# HGD_MCU_v0_2_-20200901.net
KiCad netlist of a schematic drawn in Altium Designer
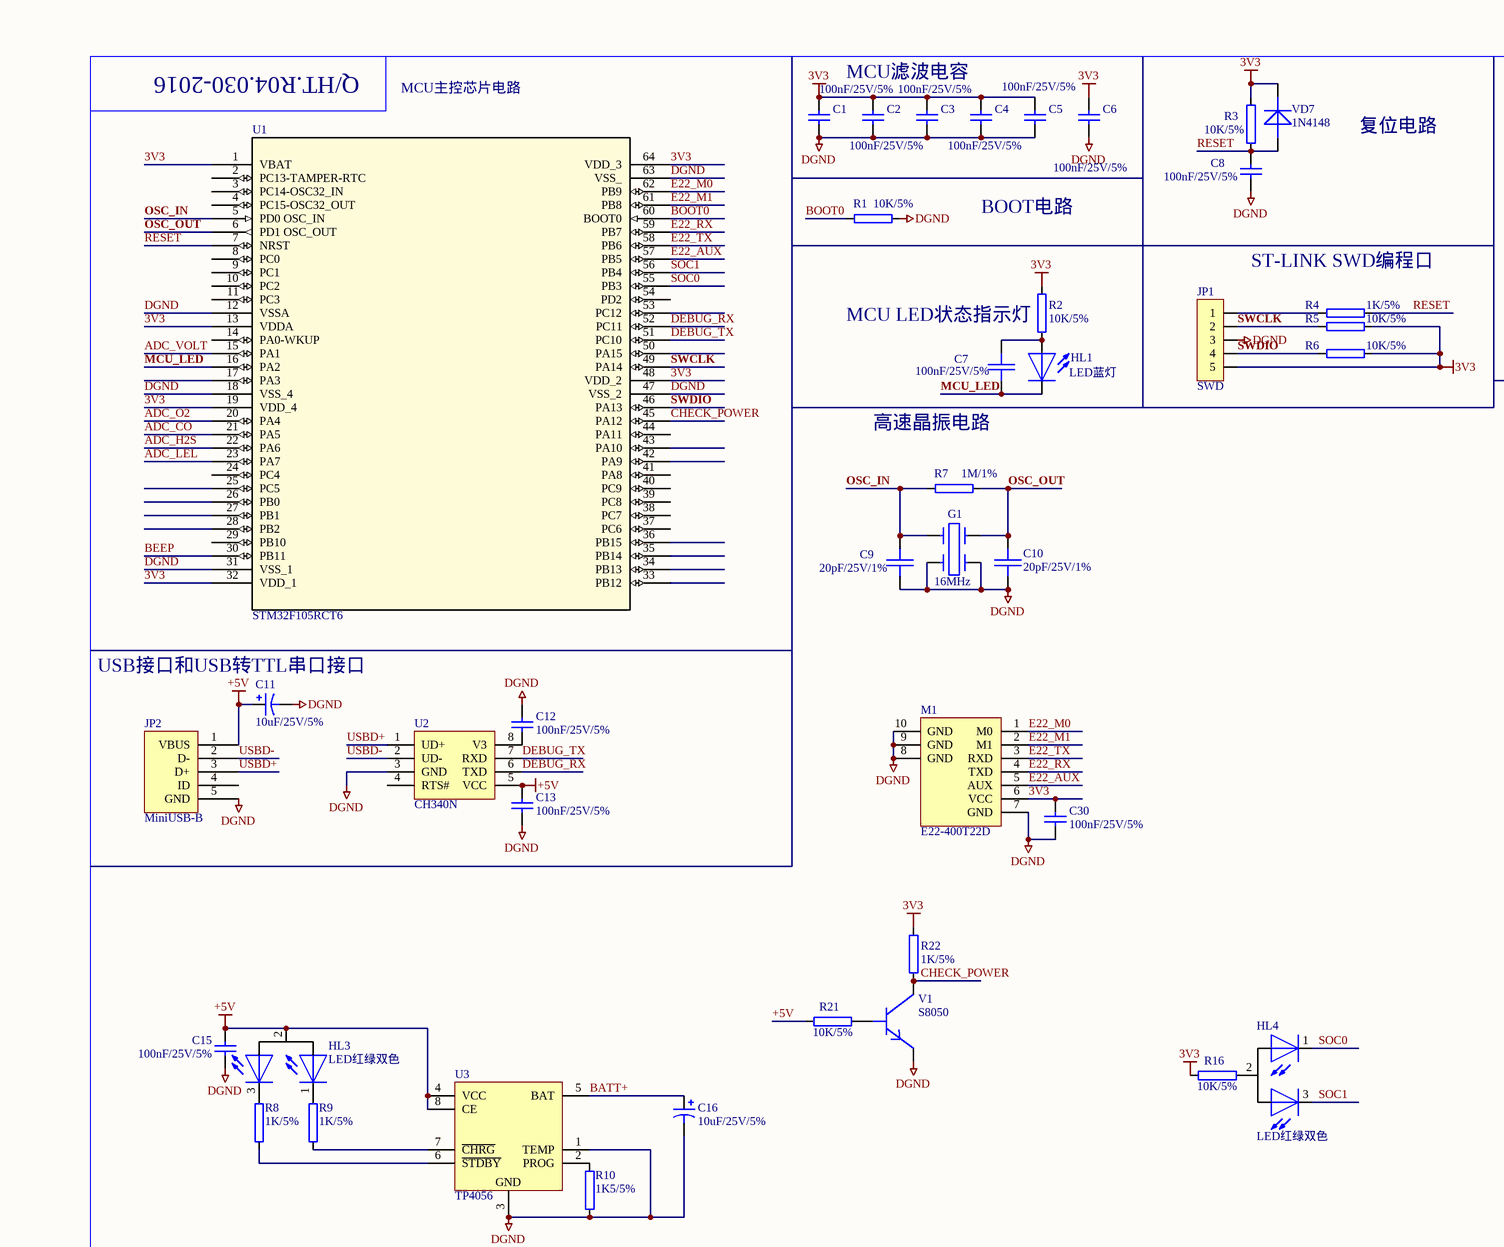
[diagram p0: HGD_MCU(v0.2)-20200901.SchDoc, top left]
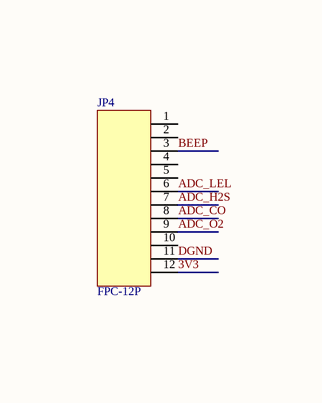
[diagram p1: HGD_MCU(v0.2)-20200901.SchDoc, top right]
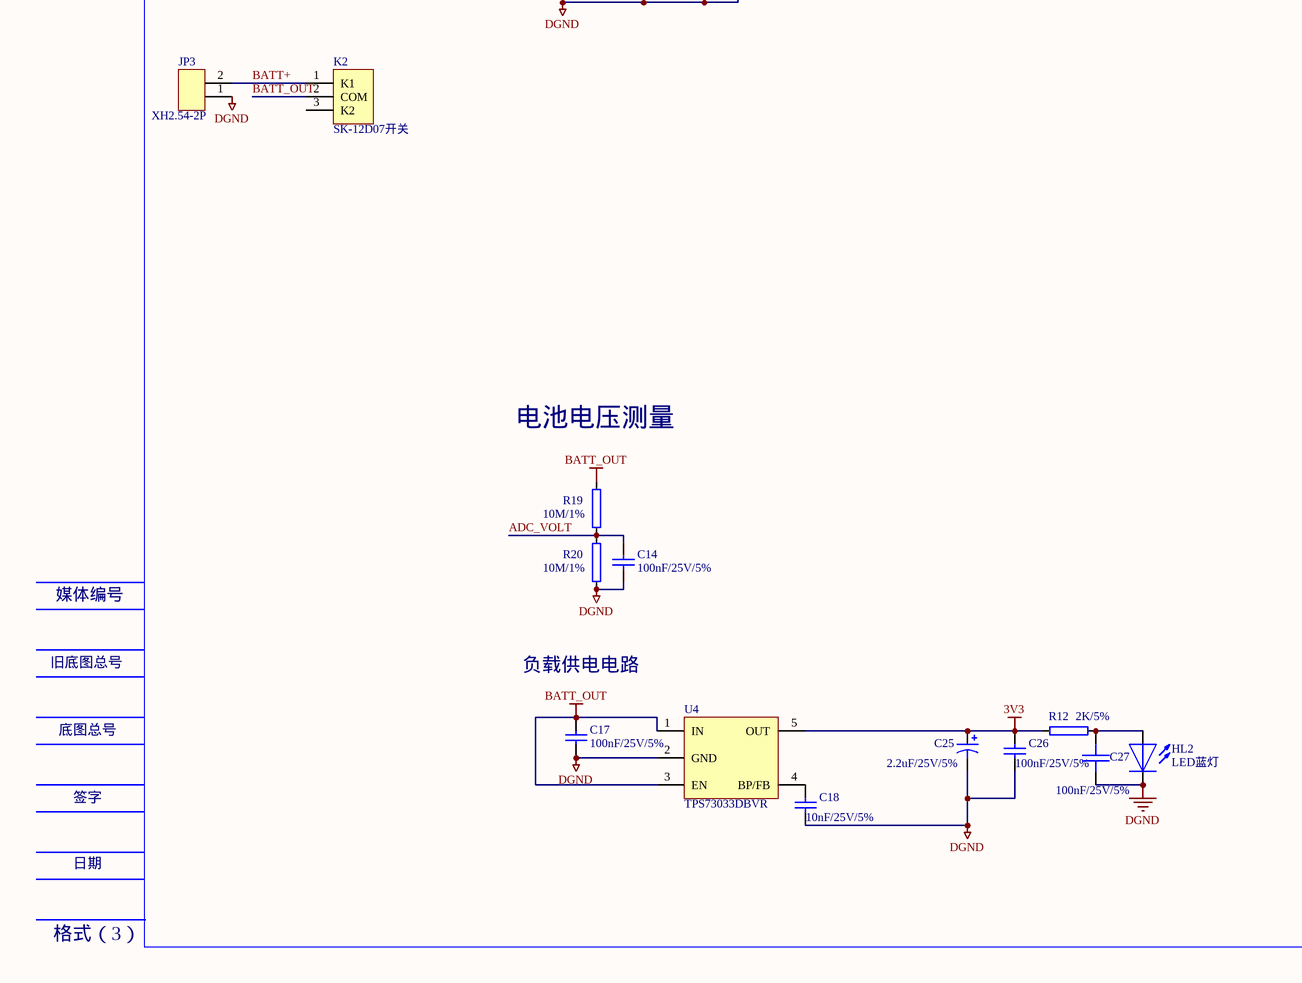
[diagram p2: HGD_MCU(v0.2)-20200901.SchDoc, bottom left]
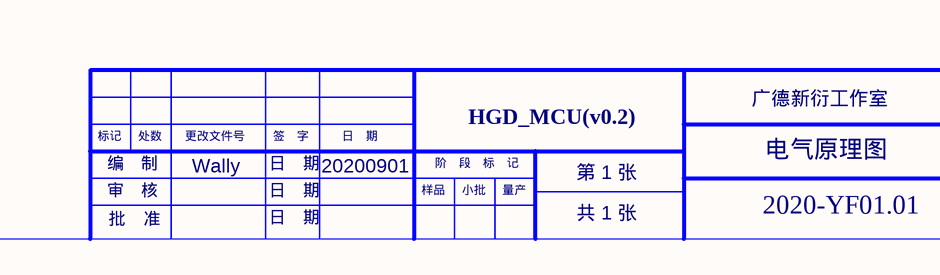
[diagram p3: HGD_MCU(v0.2)-20200901.SchDoc, bottom right]

(export (version "E")
  (design (tool "Eeschema 10.0.6"))
  (components
    (comp (ref "C1")
      (value "100nF/25V/5%")
      (footprint "C0603")
      (description "电容")
      (libsource (lib "*") (part "CAP-SMD"))
    )
    (comp (ref "C2")
      (value "100nF/25V/5%")
      (footprint "C0603")
      (description "电容")
      (libsource (lib "*") (part "CAP-SMD"))
    )
    (comp (ref "C3")
      (value "100nF/25V/5%")
      (footprint "C0603")
      (description "电容")
      (libsource (lib "*") (part "CAP-SMD"))
    )
    (comp (ref "C4")
      (value "100nF/25V/5%")
      (footprint "C0603")
      (description "电容")
      (libsource (lib "*") (part "CAP-SMD"))
    )
    (comp (ref "C5")
      (value "100nF/25V/5%")
      (footprint "C0603")
      (description "电容")
      (libsource (lib "*") (part "CAP-SMD"))
    )
    (comp (ref "C6")
      (value "100nF/25V/5%")
      (footprint "C0603")
      (description "电容")
      (libsource (lib "*") (part "CAP-SMD"))
    )
    (comp (ref "C7")
      (value "100nF/25V/5%")
      (footprint "C0603")
      (description "电容")
      (libsource (lib "*") (part "CAP"))
    )
    (comp (ref "C8")
      (value "100nF/25V/5%")
      (footprint "C0603")
      (description "电容")
      (libsource (lib "*") (part "CAP-SMD"))
    )
    (comp (ref "C9")
      (value "20pF/25V/1%")
      (footprint "C0603")
      (description "电容")
      (libsource (lib "ESSCH-Union") (part "CAP"))
    )
    (comp (ref "C10")
      (value "20pF/25V/1%")
      (footprint "C0603")
      (description "电容")
      (libsource (lib "ESSCH-Union") (part "CAP"))
    )
    (comp (ref "C11")
      (value "10uF/25V/5%")
      (footprint "C1206-1")
      (description "钽电容")
      (fields (field (name "PUBLISHER") "Altium Limited"))
      (libsource (lib "Miscellaneous Devices") (part "Cap Pol1"))
    )
    (comp (ref "C12")
      (value "100nF/25V/5%")
      (footprint "C0603")
      (description "电容")
      (fields (field (name "PUBLISHER") "Altium Limited"))
      (libsource (lib "Miscellaneous Devices") (part "Cap"))
    )
    (comp (ref "C13")
      (value "100nF/25V/5%")
      (footprint "C0603")
      (description "电容")
      (fields (field (name "PUBLISHER") "Altium Limited"))
      (libsource (lib "Miscellaneous Devices") (part "Cap"))
    )
    (comp (ref "C14") (value "100nF/25V/5%") (footprint "C0603") (libsource (lib "*") (part "CAP-SMD")))
    (comp (ref "C15")
      (value "100nF/25V/5%")
      (footprint "C0603")
      (description "电容")
      (fields (field (name "PUBLISHER") "Altium Limited"))
      (libsource (lib "Miscellaneous Devices") (part "Cap"))
    )
    (comp (ref "C16")
      (value "10uF/25V/5%")
      (footprint "C1206-1")
      (description "钽电容")
      (fields (field (name "PUBLISHER") "Altium Limited"))
      (libsource (lib "Miscellaneous Devices") (part "Cap Pol1"))
    )
    (comp (ref "C17") (value "100nF/25V/5%") (footprint "C0603") (libsource (lib "*") (part "CAP-SMD")))
    (comp (ref "C18")
      (value "10nF/25V/5%")
      (footprint "C0603")
      (description "电容")
      (fields (field (name "PUBLISHER") "Altium Limited"))
      (libsource (lib "Miscellaneous Devices") (part "Cap"))
    )
    (comp (ref "C25")
      (value "2.2uF/25V/5%")
      (footprint "C1206-1")
      (description "钽电容")
      (fields (field (name "PUBLISHER") "Altium Limited"))
      (libsource (lib "Miscellaneous Devices") (part "Cap Pol1"))
    )
    (comp (ref "C26")
      (value "100nF/25V/5%")
      (footprint "C0603")
      (description "电容")
      (fields (field (name "PUBLISHER") "Altium Limited"))
      (libsource (lib "Miscellaneous Devices") (part "Cap"))
    )
    (comp (ref "C27")
      (value "100nF/25V/5%")
      (footprint "C0603")
      (description "电容")
      (libsource (lib "*") (part "CAP"))
    )
    (comp (ref "C30")
      (value "100nF/25V/5%")
      (footprint "C0603")
      (description "电容")
      (fields (field (name "PUBLISHER") "Altium Limited"))
      (libsource (lib "Miscellaneous Devices") (part "Cap"))
    )
    (comp (ref "G1")
      (value "16MHz")
      (footprint "OSC5032")
      (description "两对电极压电晶体")
      (libsource (lib "ESSCH-Union") (part "CRYSTAL_4"))
    )
    (comp (ref "HL1")
      (value "LED蓝灯")
      (footprint "LED0603")
      (description "发光二极管")
      (libsource (lib "wypPCB_Lib") (part "发光二极管"))
    )
    (comp (ref "HL2")
      (value "LED蓝灯")
      (footprint "LED0603")
      (description "发光二极管")
      (libsource (lib "wypPCB_Lib") (part "发光二极管"))
    )
    (comp (ref "HL3")
      (value "LED红绿双色")
      (footprint "LED2_Common_Anode")
      (description "LED2_Common_Anode：双色LED，共阳极")
      (libsource (lib "wypPCB_Lib") (part "LED2_Common_Anode"))
    )
    (comp (ref "HL4")
      (value "LED红绿双色")
      (footprint "LED2_Common_Anode")
      (description "LED2_Common_Anode：双色LED，共阳极")
      (libsource (lib "") (part "LED2_Common_Anode_1"))
    )
    (comp (ref "JP1")
      (value "SWD")
      (footprint "XH2.54-5AW")
      (description "XH2.54-5P直插插针")
      (libsource (lib "wypPCB_Lib") (part "JP_XH2.54-5AW"))
    )
    (comp (ref "JP2")
      (value "MiniUSB-B")
      (footprint "MiniUSB-B")
      (description "MiniUSB-B母头插座")
      (libsource (lib "wypPCB_Lib") (part "MiniUSB-B"))
    )
    (comp (ref "JP3")
      (value "XH2.54-2P")
      (footprint "XH2.54-2AW")
      (description "XH2.54-2P弯针插座")
      (libsource (lib "wypPCB_Lib") (part "XH2.54-2AW"))
    )
    (comp (ref "JP4")
      (value "FPC-12P")
      (footprint "FPC-1.0MM-12P-W")
      (libsource (lib "wypPCB_Lib") (part "FPC-12P"))
    )
    (comp (ref "K2")
      (value "SK-12D07开关")
      (footprint "SK-12D07")
      (description "SK-12D07：3脚2档小型拨动开关")
      (libsource (lib "WTME_PT100(v0.1)-20190512") (part "SK-12D07"))
    )
    (comp (ref "M1")
      (value "E22-400T22D")
      (footprint "E22-400T22D")
      (description "E22-400T22D LoRa模块")
      (libsource (lib "wypPCB_Lib") (part "E22-400T22D"))
    )
    (comp (ref "R1")
      (value "10K/5%")
      (footprint "R0603")
      (description "电阻")
      (libsource (lib "*") (part "RES2"))
    )
    (comp (ref "R2")
      (value "10K/5%")
      (footprint "R0603")
      (description "电阻")
      (libsource (lib "*") (part "RES2"))
    )
    (comp (ref "R3")
      (value "10K/5%")
      (footprint "R0603")
      (description "电阻")
      (libsource (lib "") (part "RES2_2"))
    )
    (comp (ref "R4")
      (value "1K/5%")
      (footprint "R0603")
      (description "电阻")
      (libsource (lib "") (part "RES2_2"))
    )
    (comp (ref "R5")
      (value "10K/5%")
      (footprint "R0603")
      (description "电阻")
      (libsource (lib "") (part "RES2_2"))
    )
    (comp (ref "R6")
      (value "10K/5%")
      (footprint "R0603")
      (description "电阻")
      (libsource (lib "") (part "RES2_2"))
    )
    (comp (ref "R7")
      (value "1M/1%")
      (footprint "R0603")
      (description "电阻")
      (libsource (lib "") (part "RES2_2"))
    )
    (comp (ref "R8")
      (value "1K/5%")
      (footprint "R0603")
      (description "电阻")
      (libsource (lib "") (part "RES2_1"))
    )
    (comp (ref "R9")
      (value "1K/5%")
      (footprint "R0603")
      (description "电阻")
      (libsource (lib "") (part "RES2_1"))
    )
    (comp (ref "R10")
      (value "1K5/5%")
      (footprint "R0603")
      (description "电阻")
      (libsource (lib "") (part "RES2_1"))
    )
    (comp (ref "R12")
      (value "2K/5%")
      (footprint "R0603")
      (description "电阻")
      (libsource (lib "*") (part "RES2"))
    )
    (comp (ref "R16")
      (value "10K/5%")
      (footprint "R0603")
      (description "电阻")
      (libsource (lib "*") (part "RES2"))
    )
    (comp (ref "R19")
      (value "10M/1%")
      (footprint "R0603")
      (description "电阻")
      (libsource (lib "*") (part "RES2"))
    )
    (comp (ref "R20")
      (value "10M/1%")
      (footprint "R0603")
      (description "电阻")
      (libsource (lib "*") (part "RES2"))
    )
    (comp (ref "R21")
      (value "10K/5%")
      (footprint "R0603")
      (description "电阻")
      (libsource (lib "") (part "RES2_2"))
    )
    (comp (ref "R22")
      (value "1K/5%")
      (footprint "R0603")
      (description "电阻")
      (libsource (lib "") (part "RES2_1"))
    )
    (comp (ref "U1")
      (value "STM32F105RCT6")
      (footprint "LQFP64_STM32F105R")
      (libsource (lib "wypPCB_Lib") (part "STM32F105RCT6"))
    )
    (comp (ref "U2")
      (value "CH340N")
      (footprint "CH340N_SOP8")
      (libsource (lib "wypPCB_Lib") (part "CH340N"))
    )
    (comp (ref "U3")
      (value "TP4056")
      (footprint "TP4056_SOP8_SOP127P600X175-8N")
      (libsource (lib "wypPCB_Lib") (part "TP4056"))
    )
    (comp (ref "U4")
      (value "TPS73033DBVR")
      (footprint "SGM2019_SOT23-5_95P280X125-5N")
      (description "SGM2019：Low Power, Low Dropout, RF Linear Regulators")
      (libsource (lib "wypPCB_Lib") (part "SGM2019"))
    )
    (comp (ref "V1")
      (value "S8050")
      (footprint "SOT-23")
      (description "NPN三极管")
      (libsource (lib "ESLIB(v1.1)-AD9-20150731") (part "NPN"))
    )
    (comp (ref "VD7")
      (value "1N4148")
      (footprint "LL-34")
      (description "开关二极管")
      (libsource (lib "wypPCB_Lib") (part "开关二极管"))
    )
  )
  (nets
    (net (code "1") (name "+5V") (class "Default")
      (node (ref "C11") (pin "1") (pinfunction "1_1") (pintype "passive"))
      (node (ref "C13") (pin "1") (pinfunction "1_1") (pintype "passive"))
      (node (ref "C15") (pin "1") (pinfunction "1_1") (pintype "passive"))
      (node (ref "HL3") (pin "2") (pinfunction "A_2") (pintype "passive"))
      (node (ref "JP2") (pin "1") (pinfunction "VBUS_1") (pintype "passive"))
      (node (ref "R21") (pin "2") (pintype "passive"))
      (node (ref "U2") (pin "5") (pinfunction "VCC_5") (pintype "passive"))
      (node (ref "U3") (pin "4") (pinfunction "VCC_4") (pintype "passive"))
      (node (ref "U3") (pin "8") (pinfunction "CE_8") (pintype "passive"))
    )
    (net (code "2") (name "/ADC_CO") (class "Default")
      (node (ref "JP4") (pin "8") (pintype "passive"))
      (node (ref "U1") (pin "21") (pinfunction "PA5_21") (pintype "bidirectional"))
    )
    (net (code "3") (name "/ADC_H2S") (class "Default")
      (node (ref "JP4") (pin "7") (pintype "passive"))
      (node (ref "U1") (pin "22") (pinfunction "PA6_22") (pintype "bidirectional"))
    )
    (net (code "4") (name "/ADC_LEL") (class "Default")
      (node (ref "JP4") (pin "6") (pintype "passive"))
      (node (ref "U1") (pin "23") (pinfunction "PA7_23") (pintype "bidirectional"))
    )
    (net (code "5") (name "/ADC_O2") (class "Default")
      (node (ref "JP4") (pin "9") (pintype "passive"))
      (node (ref "U1") (pin "20") (pinfunction "PA4_20") (pintype "bidirectional"))
    )
    (net (code "6") (name "/ADC_VOLT") (class "Default")
      (node (ref "C14") (pin "1") (pintype "passive"))
      (node (ref "R19") (pin "2") (pintype "passive"))
      (node (ref "R20") (pin "1") (pintype "passive"))
      (node (ref "U1") (pin "15") (pinfunction "PA1_15") (pintype "bidirectional"))
    )
    (net (code "7") (name "/BATT+") (class "Default")
      (node (ref "C16") (pin "1") (pinfunction "1_1") (pintype "passive"))
      (node (ref "JP3") (pin "2") (pintype "passive"))
      (node (ref "K2") (pin "1") (pinfunction "K1_1") (pintype "passive"))
      (node (ref "U3") (pin "5") (pinfunction "BAT_5") (pintype "passive"))
    )
    (net (code "8") (name "/BEEP") (class "Default")
      (node (ref "JP4") (pin "3") (pintype "passive"))
      (node (ref "U1") (pin "30") (pinfunction "PB11_30") (pintype "bidirectional"))
    )
    (net (code "9") (name "/BOOT0") (class "Default")
      (node (ref "R1") (pin "2") (pintype "passive"))
      (node (ref "U1") (pin "60") (pinfunction "BOOT0_60") (pintype "input"))
    )
    (net (code "10") (name "/CHECK_POWER") (class "Default")
      (node (ref "R22") (pin "2") (pintype "passive"))
      (node (ref "U1") (pin "45") (pinfunction "PA12_45") (pintype "bidirectional"))
      (node (ref "V1") (pin "C") (pintype "passive"))
    )
    (net (code "11") (name "/DEBUG_RX") (class "Default")
      (node (ref "U1") (pin "52") (pinfunction "PC11_52") (pintype "bidirectional"))
      (node (ref "U2") (pin "6") (pinfunction "TXD_6") (pintype "passive"))
    )
    (net (code "12") (name "/DEBUG_TX") (class "Default")
      (node (ref "U1") (pin "51") (pinfunction "PC10_51") (pintype "bidirectional"))
      (node (ref "U2") (pin "7") (pinfunction "RXD_7") (pintype "passive"))
    )
    (net (code "13") (name "/E22_AUX") (class "Default")
      (node (ref "M1") (pin "5") (pinfunction "AUX_5") (pintype "passive"))
      (node (ref "U1") (pin "57") (pinfunction "PB5_57") (pintype "bidirectional"))
    )
    (net (code "14") (name "/E22_M0") (class "Default")
      (node (ref "M1") (pin "1") (pinfunction "M0_1") (pintype "passive"))
      (node (ref "U1") (pin "62") (pinfunction "PB9_62") (pintype "bidirectional"))
    )
    (net (code "15") (name "/E22_M1") (class "Default")
      (node (ref "M1") (pin "2") (pinfunction "M1_2") (pintype "passive"))
      (node (ref "U1") (pin "61") (pinfunction "PB8_61") (pintype "bidirectional"))
    )
    (net (code "16") (name "/E22_RX") (class "Default")
      (node (ref "M1") (pin "4") (pinfunction "TXD_4") (pintype "passive"))
      (node (ref "U1") (pin "59") (pinfunction "PB7_59") (pintype "bidirectional"))
    )
    (net (code "17") (name "/E22_TX") (class "Default")
      (node (ref "M1") (pin "3") (pinfunction "RXD_3") (pintype "passive"))
      (node (ref "U1") (pin "58") (pinfunction "PB6_58") (pintype "bidirectional"))
    )
    (net (code "18") (name "/MCU_LED") (class "Default")
      (node (ref "C7") (pin "2") (pintype "passive"))
      (node (ref "HL1") (pin "K") (pintype "passive"))
      (node (ref "U1") (pin "16") (pinfunction "PA2_16") (pintype "bidirectional"))
    )
    (net (code "19") (name "/OSC_IN") (class "Default")
      (node (ref "C9") (pin "2") (pintype "passive"))
      (node (ref "G1") (pin "1") (pintype "passive"))
      (node (ref "R7") (pin "1") (pintype "passive"))
      (node (ref "U1") (pin "5") (pinfunction "PD0_OSC_IN_5") (pintype "input"))
    )
    (net (code "20") (name "/OSC_OUT") (class "Default")
      (node (ref "C10") (pin "1") (pintype "passive"))
      (node (ref "G1") (pin "3") (pintype "passive"))
      (node (ref "R7") (pin "2") (pintype "passive"))
      (node (ref "U1") (pin "6") (pinfunction "PD1_OSC_OUT_6") (pintype "output"))
    )
    (net (code "21") (name "/RESET") (class "Default")
      (node (ref "C8") (pin "1") (pintype "passive"))
      (node (ref "R3") (pin "1") (pintype "passive"))
      (node (ref "R4") (pin "2") (pintype "passive"))
      (node (ref "U1") (pin "7") (pinfunction "NRST_7") (pintype "bidirectional"))
      (node (ref "VD7") (pin "A") (pintype "passive"))
    )
    (net (code "22") (name "/SOC0") (class "Default")
      (node (ref "HL4") (pin "1") (pinfunction "K1_1") (pintype "passive"))
      (node (ref "U1") (pin "55") (pinfunction "PB3_55") (pintype "bidirectional"))
    )
    (net (code "23") (name "/SOC1") (class "Default")
      (node (ref "HL4") (pin "3") (pinfunction "K2_3") (pintype "passive"))
      (node (ref "U1") (pin "56") (pinfunction "PB4_56") (pintype "bidirectional"))
    )
    (net (code "24") (name "/SWCLK") (class "Default")
      (node (ref "JP1") (pin "2") (pinfunction "2_2") (pintype "passive"))
      (node (ref "R5") (pin "1") (pintype "passive"))
      (node (ref "U1") (pin "49") (pinfunction "PA14_49") (pintype "bidirectional"))
    )
    (net (code "25") (name "/SWDIO") (class "Default")
      (node (ref "JP1") (pin "4") (pinfunction "4_4") (pintype "passive"))
      (node (ref "R6") (pin "1") (pintype "passive"))
      (node (ref "U1") (pin "46") (pinfunction "PA13_46") (pintype "bidirectional"))
    )
    (net (code "26") (name "/USBD+") (class "Default")
      (node (ref "JP2") (pin "3") (pinfunction "D+_3") (pintype "passive"))
      (node (ref "U2") (pin "1") (pinfunction "UD+_1") (pintype "passive"))
    )
    (net (code "27") (name "/USBD-") (class "Default")
      (node (ref "JP2") (pin "2") (pinfunction "D-_2") (pintype "passive"))
      (node (ref "U2") (pin "2") (pinfunction "UD-_2") (pintype "passive"))
    )
    (net (code "28") (name "3V3") (class "Default")
      (node (ref "C1") (pin "2") (pintype "passive"))
      (node (ref "C2") (pin "1") (pintype "passive"))
      (node (ref "C25") (pin "1") (pinfunction "1_1") (pintype "passive"))
      (node (ref "C26") (pin "2") (pinfunction "2_2") (pintype "passive"))
      (node (ref "C3") (pin "1") (pintype "passive"))
      (node (ref "C30") (pin "2") (pinfunction "2_2") (pintype "passive"))
      (node (ref "C4") (pin "2") (pintype "passive"))
      (node (ref "C5") (pin "2") (pintype "passive"))
      (node (ref "C6") (pin "2") (pintype "passive"))
      (node (ref "JP1") (pin "5") (pinfunction "5_5") (pintype "passive"))
      (node (ref "JP4") (pin "12") (pintype "passive"))
      (node (ref "M1") (pin "6") (pinfunction "VCC_6") (pintype "passive"))
      (node (ref "R12") (pin "1") (pintype "passive"))
      (node (ref "R16") (pin "1") (pintype "passive"))
      (node (ref "R2") (pin "1") (pintype "passive"))
      (node (ref "R22") (pin "1") (pintype "passive"))
      (node (ref "R3") (pin "2") (pintype "passive"))
      (node (ref "R5") (pin "2") (pintype "passive"))
      (node (ref "R6") (pin "2") (pintype "passive"))
      (node (ref "U1") (pin "1") (pinfunction "VBAT_1") (pintype "power_in"))
      (node (ref "U1") (pin "13") (pinfunction "VDDA_13") (pintype "power_in"))
      (node (ref "U1") (pin "19") (pinfunction "VDD_4_19") (pintype "power_in"))
      (node (ref "U1") (pin "32") (pinfunction "VDD_1_32") (pintype "power_in"))
      (node (ref "U1") (pin "48") (pinfunction "VDD_2_48") (pintype "power_in"))
      (node (ref "U1") (pin "64") (pinfunction "VDD_3_64") (pintype "power_in"))
      (node (ref "U4") (pin "5") (pinfunction "OUT_5") (pintype "passive"))
      (node (ref "VD7") (pin "K") (pintype "passive"))
    )
    (net (code "29") (name "BATT_OUT") (class "Default")
      (node (ref "C17") (pin "1") (pintype "passive"))
      (node (ref "K2") (pin "2") (pinfunction "COM_2") (pintype "passive"))
      (node (ref "R19") (pin "1") (pintype "passive"))
      (node (ref "U4") (pin "1") (pinfunction "IN_1") (pintype "passive"))
      (node (ref "U4") (pin "3") (pinfunction "EN_3") (pintype "passive"))
    )
    (net (code "30") (name "DGND") (class "Default")
      (node (ref "C1") (pin "1") (pintype "passive"))
      (node (ref "C10") (pin "2") (pintype "passive"))
      (node (ref "C11") (pin "2") (pinfunction "2_2") (pintype "passive"))
      (node (ref "C12") (pin "1") (pinfunction "1_1") (pintype "passive"))
      (node (ref "C13") (pin "2") (pinfunction "2_2") (pintype "passive"))
      (node (ref "C14") (pin "2") (pintype "passive"))
      (node (ref "C15") (pin "2") (pinfunction "2_2") (pintype "passive"))
      (node (ref "C16") (pin "2") (pinfunction "2_2") (pintype "passive"))
      (node (ref "C17") (pin "2") (pintype "passive"))
      (node (ref "C18") (pin "1") (pinfunction "1_1") (pintype "passive"))
      (node (ref "C2") (pin "2") (pintype "passive"))
      (node (ref "C25") (pin "2") (pinfunction "2_2") (pintype "passive"))
      (node (ref "C26") (pin "1") (pinfunction "1_1") (pintype "passive"))
      (node (ref "C27") (pin "2") (pintype "passive"))
      (node (ref "C3") (pin "2") (pintype "passive"))
      (node (ref "C30") (pin "1") (pinfunction "1_1") (pintype "passive"))
      (node (ref "C4") (pin "1") (pintype "passive"))
      (node (ref "C5") (pin "1") (pintype "passive"))
      (node (ref "C6") (pin "1") (pintype "passive"))
      (node (ref "C8") (pin "2") (pintype "passive"))
      (node (ref "C9") (pin "1") (pintype "passive"))
      (node (ref "G1") (pin "2") (pintype "passive"))
      (node (ref "G1") (pin "4") (pintype "passive"))
      (node (ref "HL2") (pin "K") (pintype "passive"))
      (node (ref "JP1") (pin "3") (pinfunction "3_3") (pintype "passive"))
      (node (ref "JP2") (pin "5") (pinfunction "GND_5") (pintype "passive"))
      (node (ref "JP3") (pin "1") (pintype "passive"))
      (node (ref "JP4") (pin "11") (pintype "passive"))
      (node (ref "M1") (pin "10") (pinfunction "GND_10") (pintype "passive"))
      (node (ref "M1") (pin "7") (pinfunction "GND_7") (pintype "passive"))
      (node (ref "M1") (pin "8") (pinfunction "GND_8") (pintype "passive"))
      (node (ref "M1") (pin "9") (pinfunction "GND_9") (pintype "passive"))
      (node (ref "R1") (pin "1") (pintype "passive"))
      (node (ref "R10") (pin "1") (pintype "passive"))
      (node (ref "R20") (pin "2") (pintype "passive"))
      (node (ref "U1") (pin "12") (pinfunction "VSSA_12") (pintype "power_in"))
      (node (ref "U1") (pin "18") (pinfunction "VSS_4_18") (pintype "power_in"))
      (node (ref "U1") (pin "31") (pinfunction "VSS_1_31") (pintype "power_in"))
      (node (ref "U1") (pin "47") (pinfunction "VSS_2_47") (pintype "power_in"))
      (node (ref "U1") (pin "63") (pinfunction "VSS__63") (pintype "power_in"))
      (node (ref "U2") (pin "3") (pinfunction "GND_3") (pintype "passive"))
      (node (ref "U3") (pin "1") (pinfunction "TEMP_1") (pintype "passive"))
      (node (ref "U3") (pin "3") (pinfunction "GND_3") (pintype "passive"))
      (node (ref "U4") (pin "2") (pinfunction "GND_2") (pintype "passive"))
      (node (ref "V1") (pin "E") (pintype "passive"))
    )
    (net (code "31") (name "Net-(C7-Pad1)") (class "Default")
      (node (ref "C7") (pin "1") (pintype "passive"))
      (node (ref "HL1") (pin "A") (pintype "passive"))
      (node (ref "R2") (pin "2") (pintype "passive"))
    )
    (net (code "32") (name "Net-(C27-Pad1)") (class "Default")
      (node (ref "C27") (pin "1") (pintype "passive"))
      (node (ref "HL2") (pin "A") (pintype "passive"))
      (node (ref "R12") (pin "2") (pintype "passive"))
    )
    (net (code "33") (name "Net-(HL3-K1)") (class "Default")
      (node (ref "HL3") (pin "1") (pinfunction "K1_1") (pintype "passive"))
      (node (ref "R9") (pin "2") (pintype "passive"))
    )
    (net (code "34") (name "Net-(HL3-K2)") (class "Default")
      (node (ref "HL3") (pin "3") (pinfunction "K2_3") (pintype "passive"))
      (node (ref "R8") (pin "2") (pintype "passive"))
    )
    (net (code "35") (name "Net-(HL4-A)") (class "Default")
      (node (ref "HL4") (pin "2") (pinfunction "A_2") (pintype "passive"))
      (node (ref "R16") (pin "2") (pintype "passive"))
    )
    (net (code "36") (name "Net-(JP1-Pad1)") (class "Default")
      (node (ref "JP1") (pin "1") (pinfunction "1_1") (pintype "passive"))
      (node (ref "R4") (pin "1") (pintype "passive"))
    )
    (net (code "37") (name "Net-(R21-Pad1)") (class "Default")
      (node (ref "R21") (pin "1") (pintype "passive"))
      (node (ref "V1") (pin "B") (pintype "passive"))
    )
    (net (code "38") (name "Net-(U2-V3)") (class "Default")
      (node (ref "C12") (pin "2") (pinfunction "2_2") (pintype "passive"))
      (node (ref "U2") (pin "8") (pinfunction "V3_8") (pintype "passive"))
    )
    (net (code "39") (name "Net-(U3-PROG)") (class "Default")
      (node (ref "R10") (pin "2") (pintype "passive"))
      (node (ref "U3") (pin "2") (pinfunction "PROG_2") (pintype "passive"))
    )
    (net (code "40") (name "Net-(U3-~{CHRG})") (class "Default")
      (node (ref "R9") (pin "1") (pintype "passive"))
      (node (ref "U3") (pin "7") (pinfunction "~{CHRG}_7") (pintype "passive"))
    )
    (net (code "41") (name "Net-(U3-~{STDBY})") (class "Default")
      (node (ref "R8") (pin "1") (pintype "passive"))
      (node (ref "U3") (pin "6") (pinfunction "~{STDBY}_6") (pintype "passive"))
    )
    (net (code "42") (name "Net-(U4-BP{slash}FB)") (class "Default")
      (node (ref "C18") (pin "2") (pinfunction "2_2") (pintype "passive"))
      (node (ref "U4") (pin "4") (pinfunction "BP/FB_4") (pintype "passive"))
    )
    (net (code "43") (name "unconnected-(JP2-ID-Pad4)") (class "Default")
      (node (ref "JP2") (pin "4") (pinfunction "ID_4") (pintype "passive"))
    )
    (net (code "44") (name "unconnected-(JP4-Pad1)") (class "Default")
      (node (ref "JP4") (pin "1") (pintype "passive"))
    )
    (net (code "45") (name "unconnected-(JP4-Pad2)") (class "Default")
      (node (ref "JP4") (pin "2") (pintype "passive"))
    )
    (net (code "46") (name "unconnected-(JP4-Pad4)") (class "Default")
      (node (ref "JP4") (pin "4") (pintype "passive"))
    )
    (net (code "47") (name "unconnected-(JP4-Pad5)") (class "Default")
      (node (ref "JP4") (pin "5") (pintype "passive"))
    )
    (net (code "48") (name "unconnected-(JP4-Pad10)") (class "Default")
      (node (ref "JP4") (pin "10") (pintype "passive"))
    )
    (net (code "49") (name "unconnected-(K2-K2-Pad3)") (class "Default")
      (node (ref "K2") (pin "3") (pinfunction "K2_3") (pintype "passive"))
    )
    (net (code "50") (name "unconnected-(U1-PA0-WKUP-Pad14)") (class "Default")
      (node (ref "U1") (pin "14") (pinfunction "PA0-WKUP_14") (pintype "bidirectional"))
    )
    (net (code "51") (name "unconnected-(U1-PA3-Pad17)") (class "Default")
      (node (ref "U1") (pin "17") (pinfunction "PA3_17") (pintype "bidirectional"))
    )
    (net (code "52") (name "unconnected-(U1-PA8-Pad41)") (class "Default")
      (node (ref "U1") (pin "41") (pinfunction "PA8_41") (pintype "bidirectional"))
    )
    (net (code "53") (name "unconnected-(U1-PA9-Pad42)") (class "Default")
      (node (ref "U1") (pin "42") (pinfunction "PA9_42") (pintype "bidirectional"))
    )
    (net (code "54") (name "unconnected-(U1-PA10-Pad43)") (class "Default")
      (node (ref "U1") (pin "43") (pinfunction "PA10_43") (pintype "bidirectional"))
    )
    (net (code "55") (name "unconnected-(U1-PA11-Pad44)") (class "Default")
      (node (ref "U1") (pin "44") (pinfunction "PA11_44") (pintype "bidirectional"))
    )
    (net (code "56") (name "unconnected-(U1-PA15-Pad50)") (class "Default")
      (node (ref "U1") (pin "50") (pinfunction "PA15_50") (pintype "bidirectional"))
    )
    (net (code "57") (name "unconnected-(U1-PB0-Pad26)") (class "Default")
      (node (ref "U1") (pin "26") (pinfunction "PB0_26") (pintype "bidirectional"))
    )
    (net (code "58") (name "unconnected-(U1-PB1-Pad27)") (class "Default")
      (node (ref "U1") (pin "27") (pinfunction "PB1_27") (pintype "bidirectional"))
    )
    (net (code "59") (name "unconnected-(U1-PB2-Pad28)") (class "Default")
      (node (ref "U1") (pin "28") (pinfunction "PB2_28") (pintype "bidirectional"))
    )
    (net (code "60") (name "unconnected-(U1-PB10-Pad29)") (class "Default")
      (node (ref "U1") (pin "29") (pinfunction "PB10_29") (pintype "bidirectional"))
    )
    (net (code "61") (name "unconnected-(U1-PB12-Pad33)") (class "Default")
      (node (ref "U1") (pin "33") (pinfunction "PB12_33") (pintype "bidirectional"))
    )
    (net (code "62") (name "unconnected-(U1-PB13-Pad34)") (class "Default")
      (node (ref "U1") (pin "34") (pinfunction "PB13_34") (pintype "bidirectional"))
    )
    (net (code "63") (name "unconnected-(U1-PB14-Pad35)") (class "Default")
      (node (ref "U1") (pin "35") (pinfunction "PB14_35") (pintype "bidirectional"))
    )
    (net (code "64") (name "unconnected-(U1-PB15-Pad36)") (class "Default")
      (node (ref "U1") (pin "36") (pinfunction "PB15_36") (pintype "bidirectional"))
    )
    (net (code "65") (name "unconnected-(U1-PC0-Pad8)") (class "Default")
      (node (ref "U1") (pin "8") (pinfunction "PC0_8") (pintype "bidirectional"))
    )
    (net (code "66") (name "unconnected-(U1-PC1-Pad9)") (class "Default")
      (node (ref "U1") (pin "9") (pinfunction "PC1_9") (pintype "bidirectional"))
    )
    (net (code "67") (name "unconnected-(U1-PC2-Pad10)") (class "Default")
      (node (ref "U1") (pin "10") (pinfunction "PC2_10") (pintype "bidirectional"))
    )
    (net (code "68") (name "unconnected-(U1-PC3-Pad11)") (class "Default")
      (node (ref "U1") (pin "11") (pinfunction "PC3_11") (pintype "bidirectional"))
    )
    (net (code "69") (name "unconnected-(U1-PC4-Pad24)") (class "Default")
      (node (ref "U1") (pin "24") (pinfunction "PC4_24") (pintype "bidirectional"))
    )
    (net (code "70") (name "unconnected-(U1-PC5-Pad25)") (class "Default")
      (node (ref "U1") (pin "25") (pinfunction "PC5_25") (pintype "bidirectional"))
    )
    (net (code "71") (name "unconnected-(U1-PC6-Pad37)") (class "Default")
      (node (ref "U1") (pin "37") (pinfunction "PC6_37") (pintype "bidirectional"))
    )
    (net (code "72") (name "unconnected-(U1-PC7-Pad38)") (class "Default")
      (node (ref "U1") (pin "38") (pinfunction "PC7_38") (pintype "bidirectional"))
    )
    (net (code "73") (name "unconnected-(U1-PC8-Pad39)") (class "Default")
      (node (ref "U1") (pin "39") (pinfunction "PC8_39") (pintype "bidirectional"))
    )
    (net (code "74") (name "unconnected-(U1-PC9-Pad40)") (class "Default")
      (node (ref "U1") (pin "40") (pinfunction "PC9_40") (pintype "bidirectional"))
    )
    (net (code "75") (name "unconnected-(U1-PC12-Pad53)") (class "Default")
      (node (ref "U1") (pin "53") (pinfunction "PC12_53") (pintype "bidirectional"))
    )
    (net (code "76") (name "unconnected-(U1-PC13-TAMPER-RTC-Pad2)") (class "Default")
      (node (ref "U1") (pin "2") (pinfunction "PC13-TAMPER-RTC_2") (pintype "bidirectional"))
    )
    (net (code "77") (name "unconnected-(U1-PC14-OSC32_IN-Pad3)") (class "Default")
      (node (ref "U1") (pin "3") (pinfunction "PC14-OSC32_IN_3") (pintype "bidirectional"))
    )
    (net (code "78") (name "unconnected-(U1-PC15-OSC32_OUT-Pad4)") (class "Default")
      (node (ref "U1") (pin "4") (pinfunction "PC15-OSC32_OUT_4") (pintype "bidirectional"))
    )
    (net (code "79") (name "unconnected-(U1-PD2-Pad54)") (class "Default")
      (node (ref "U1") (pin "54") (pinfunction "PD2_54") (pintype "bidirectional"))
    )
    (net (code "80") (name "unconnected-(U2-RTS#-Pad4)") (class "Default")
      (node (ref "U2") (pin "4") (pinfunction "RTS#_4") (pintype "passive"))
    )
  )
)
